# clock_mux.net
KiCad netlist of a schematic drawn in Altium Designer
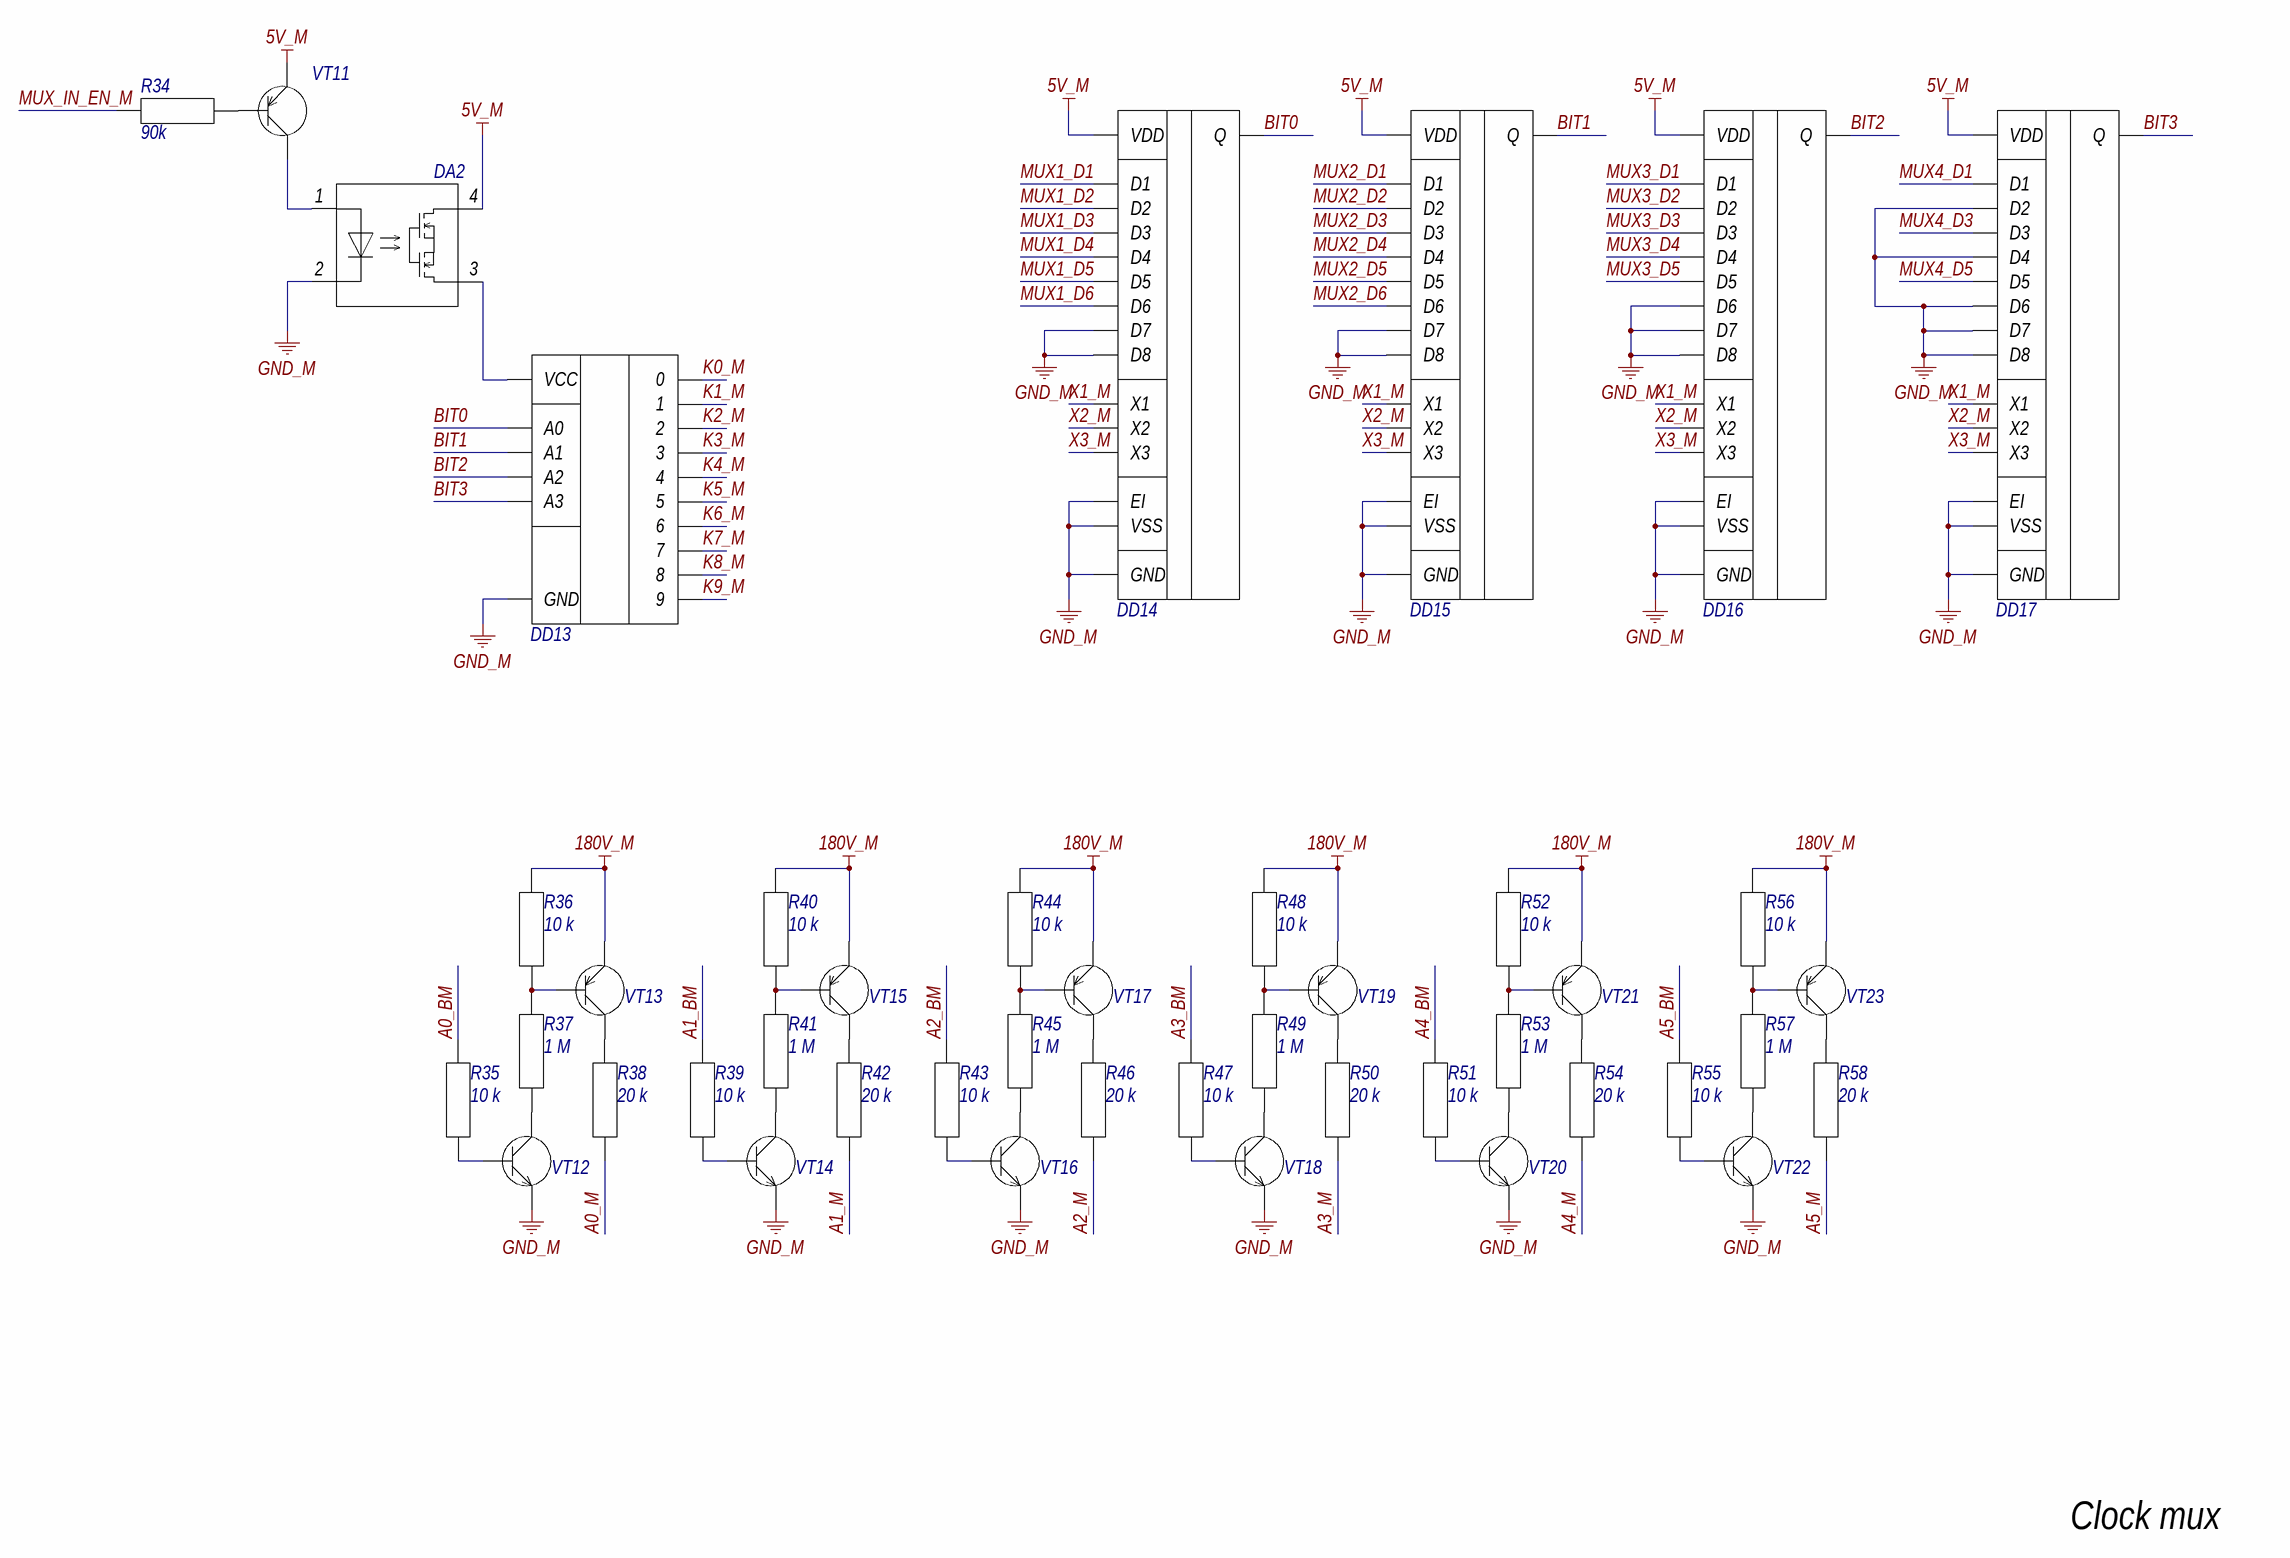
[diagram p0: clock_mux.SchDoc]

(export (version "E")
  (design (tool "Eeschema 10.0.6"))
  (components
    (comp (ref "DA2")
      (value "CPC1008NTR")
      (footprint "CPC1008NTR")
      (libsource (lib "Schlib1") (part "CPC1008NTR"))
    )
    (comp (ref "DD13") (value "К155ИД1") (footprint "DIP-16") (libsource (lib "Schlib1") (part "К155ИД1")))
    (comp (ref "DD14") (value "К561КП2") (footprint "DIP-16") (libsource (lib "Schlib1") (part "К561КП2")))
    (comp (ref "DD15") (value "К561КП2") (footprint "DIP-16") (libsource (lib "Schlib1") (part "К561КП2")))
    (comp (ref "DD16") (value "К561КП2") (footprint "DIP-16") (libsource (lib "Schlib1") (part "К561КП2")))
    (comp (ref "DD17") (value "К561КП2") (footprint "DIP-16") (libsource (lib "Schlib1") (part "К561КП2")))
    (comp (ref "R34")
      (value "90k")
      (footprint "RES-DIP")
      (fields (field (name "Comment") "R"))
      (libsource (lib "") (part "R_2"))
    )
    (comp (ref "R35")
      (value "10 k")
      (footprint "RES-DIP-V")
      (fields (field (name "Comment") "R"))
      (libsource (lib "") (part "R_1"))
    )
    (comp (ref "R36")
      (value "10 k")
      (footprint "RES-DIP-V")
      (fields (field (name "Comment") "R"))
      (libsource (lib "Schlib1") (part "R"))
    )
    (comp (ref "R37")
      (value "1 M")
      (footprint "RES-DIP-V")
      (fields (field (name "Comment") "R"))
      (libsource (lib "Schlib1") (part "R"))
    )
    (comp (ref "R38")
      (value "20 k")
      (footprint "RES-DIP-V")
      (fields (field (name "Comment") "R"))
      (libsource (lib "Schlib1") (part "R"))
    )
    (comp (ref "R39")
      (value "10 k")
      (footprint "RES-DIP-V")
      (fields (field (name "Comment") "R"))
      (libsource (lib "") (part "R_1"))
    )
    (comp (ref "R40")
      (value "10 k")
      (footprint "RES-DIP-V")
      (fields (field (name "Comment") "R"))
      (libsource (lib "Schlib1") (part "R"))
    )
    (comp (ref "R41")
      (value "1 M")
      (footprint "RES-DIP-V")
      (fields (field (name "Comment") "R"))
      (libsource (lib "Schlib1") (part "R"))
    )
    (comp (ref "R42")
      (value "20 k")
      (footprint "RES-DIP-V")
      (fields (field (name "Comment") "R"))
      (libsource (lib "Schlib1") (part "R"))
    )
    (comp (ref "R43")
      (value "10 k")
      (footprint "RES-DIP-V")
      (fields (field (name "Comment") "R"))
      (libsource (lib "") (part "R_1"))
    )
    (comp (ref "R44")
      (value "10 k")
      (footprint "RES-DIP-V")
      (fields (field (name "Comment") "R"))
      (libsource (lib "Schlib1") (part "R"))
    )
    (comp (ref "R45")
      (value "1 M")
      (footprint "RES-DIP-V")
      (fields (field (name "Comment") "R"))
      (libsource (lib "Schlib1") (part "R"))
    )
    (comp (ref "R46")
      (value "20 k")
      (footprint "RES-DIP-V")
      (fields (field (name "Comment") "R"))
      (libsource (lib "Schlib1") (part "R"))
    )
    (comp (ref "R47")
      (value "10 k")
      (footprint "RES-DIP-V")
      (fields (field (name "Comment") "R"))
      (libsource (lib "") (part "R_1"))
    )
    (comp (ref "R48")
      (value "10 k")
      (footprint "RES-DIP-V")
      (fields (field (name "Comment") "R"))
      (libsource (lib "Schlib1") (part "R"))
    )
    (comp (ref "R49")
      (value "1 M")
      (footprint "RES-DIP-V")
      (fields (field (name "Comment") "R"))
      (libsource (lib "Schlib1") (part "R"))
    )
    (comp (ref "R50")
      (value "20 k")
      (footprint "RES-DIP-V")
      (fields (field (name "Comment") "R"))
      (libsource (lib "Schlib1") (part "R"))
    )
    (comp (ref "R51")
      (value "10 k")
      (footprint "RES-DIP-V")
      (fields (field (name "Comment") "R"))
      (libsource (lib "") (part "R_1"))
    )
    (comp (ref "R52")
      (value "10 k")
      (footprint "RES-DIP-V")
      (fields (field (name "Comment") "R"))
      (libsource (lib "Schlib1") (part "R"))
    )
    (comp (ref "R53")
      (value "1 M")
      (footprint "RES-DIP-V")
      (fields (field (name "Comment") "R"))
      (libsource (lib "Schlib1") (part "R"))
    )
    (comp (ref "R54")
      (value "20 k")
      (footprint "RES-DIP-V")
      (fields (field (name "Comment") "R"))
      (libsource (lib "Schlib1") (part "R"))
    )
    (comp (ref "R55")
      (value "10 k")
      (footprint "RES-DIP-V")
      (fields (field (name "Comment") "R"))
      (libsource (lib "") (part "R_1"))
    )
    (comp (ref "R56")
      (value "10 k")
      (footprint "RES-DIP-V")
      (fields (field (name "Comment") "R"))
      (libsource (lib "Schlib1") (part "R"))
    )
    (comp (ref "R57")
      (value "1 M")
      (footprint "RES-DIP-V")
      (fields (field (name "Comment") "R"))
      (libsource (lib "Schlib1") (part "R"))
    )
    (comp (ref "R58")
      (value "20 k")
      (footprint "RES-DIP-V")
      (fields (field (name "Comment") "R"))
      (libsource (lib "Schlib1") (part "R"))
    )
    (comp (ref "VT11") (value "BC327") (footprint "BC327") (libsource (lib "Schlib1") (part "BC327")))
    (comp (ref "VT12") (value "2N5551") (footprint "2N5551") (libsource (lib "Schlib1") (part "2N5551")))
    (comp (ref "VT13") (value "2N5401") (footprint "2N5401") (libsource (lib "Schlib1") (part "2N5401")))
    (comp (ref "VT14") (value "2N5551") (footprint "2N5551") (libsource (lib "Schlib1") (part "2N5551")))
    (comp (ref "VT15") (value "2N5401") (footprint "2N5401") (libsource (lib "Schlib1") (part "2N5401")))
    (comp (ref "VT16") (value "2N5551") (footprint "2N5551") (libsource (lib "Schlib1") (part "2N5551")))
    (comp (ref "VT17") (value "2N5401") (footprint "2N5401") (libsource (lib "Schlib1") (part "2N5401")))
    (comp (ref "VT18") (value "2N5551") (footprint "2N5551") (libsource (lib "Schlib1") (part "2N5551")))
    (comp (ref "VT19") (value "2N5401") (footprint "2N5401") (libsource (lib "Schlib1") (part "2N5401")))
    (comp (ref "VT20") (value "2N5551") (footprint "2N5551") (libsource (lib "Schlib1") (part "2N5551")))
    (comp (ref "VT21") (value "2N5401") (footprint "2N5401") (libsource (lib "Schlib1") (part "2N5401")))
    (comp (ref "VT22") (value "2N5551") (footprint "2N5551") (libsource (lib "Schlib1") (part "2N5551")))
    (comp (ref "VT23") (value "2N5401") (footprint "2N5401") (libsource (lib "Schlib1") (part "2N5401")))
  )
  (nets
    (net (code "1") (name "/A0_BM") (class "Default")
      (node (ref "R35") (pin "1") (pinfunction "1_1") (pintype "passive"))
    )
    (net (code "2") (name "/A0_M") (class "Default")
      (node (ref "R38") (pin "1") (pinfunction "1_1") (pintype "passive"))
    )
    (net (code "3") (name "/A1_BM") (class "Default")
      (node (ref "R39") (pin "1") (pinfunction "1_1") (pintype "passive"))
    )
    (net (code "4") (name "/A1_M") (class "Default")
      (node (ref "R42") (pin "1") (pinfunction "1_1") (pintype "passive"))
    )
    (net (code "5") (name "/A2_BM") (class "Default")
      (node (ref "R43") (pin "1") (pinfunction "1_1") (pintype "passive"))
    )
    (net (code "6") (name "/A2_M") (class "Default")
      (node (ref "R46") (pin "1") (pinfunction "1_1") (pintype "passive"))
    )
    (net (code "7") (name "/A3_BM") (class "Default")
      (node (ref "R47") (pin "1") (pinfunction "1_1") (pintype "passive"))
    )
    (net (code "8") (name "/A3_M") (class "Default")
      (node (ref "R50") (pin "1") (pinfunction "1_1") (pintype "passive"))
    )
    (net (code "9") (name "/A4_BM") (class "Default")
      (node (ref "R51") (pin "1") (pinfunction "1_1") (pintype "passive"))
    )
    (net (code "10") (name "/A4_M") (class "Default")
      (node (ref "R54") (pin "1") (pinfunction "1_1") (pintype "passive"))
    )
    (net (code "11") (name "/A5_BM") (class "Default")
      (node (ref "R55") (pin "1") (pinfunction "1_1") (pintype "passive"))
    )
    (net (code "12") (name "/A5_M") (class "Default")
      (node (ref "R58") (pin "1") (pinfunction "1_1") (pintype "passive"))
    )
    (net (code "13") (name "/BIT0") (class "Default")
      (node (ref "DD13") (pin "3") (pinfunction "A0_3") (pintype "passive"))
      (node (ref "DD14") (pin "3") (pinfunction "Q_3") (pintype "passive"))
    )
    (net (code "14") (name "/BIT1") (class "Default")
      (node (ref "DD13") (pin "6") (pinfunction "A1_6") (pintype "passive"))
      (node (ref "DD15") (pin "3") (pinfunction "Q_3") (pintype "passive"))
    )
    (net (code "15") (name "/BIT2") (class "Default")
      (node (ref "DD13") (pin "7") (pinfunction "A2_7") (pintype "passive"))
      (node (ref "DD16") (pin "3") (pinfunction "Q_3") (pintype "passive"))
    )
    (net (code "16") (name "/BIT3") (class "Default")
      (node (ref "DD13") (pin "4") (pinfunction "A3_4") (pintype "passive"))
      (node (ref "DD17") (pin "3") (pinfunction "Q_3") (pintype "passive"))
    )
    (net (code "17") (name "/K0_M") (class "Default")
      (node (ref "DD13") (pin "16") (pinfunction "0_16") (pintype "passive"))
    )
    (net (code "18") (name "/K1_M") (class "Default")
      (node (ref "DD13") (pin "15") (pinfunction "1_15") (pintype "passive"))
    )
    (net (code "19") (name "/K2_M") (class "Default")
      (node (ref "DD13") (pin "8") (pinfunction "2_8") (pintype "passive"))
    )
    (net (code "20") (name "/K3_M") (class "Default")
      (node (ref "DD13") (pin "9") (pinfunction "3_9") (pintype "passive"))
    )
    (net (code "21") (name "/K4_M") (class "Default")
      (node (ref "DD13") (pin "13") (pinfunction "4_13") (pintype "passive"))
    )
    (net (code "22") (name "/K5_M") (class "Default")
      (node (ref "DD13") (pin "14") (pinfunction "5_14") (pintype "passive"))
    )
    (net (code "23") (name "/K6_M") (class "Default")
      (node (ref "DD13") (pin "11") (pinfunction "6_11") (pintype "passive"))
    )
    (net (code "24") (name "/K7_M") (class "Default")
      (node (ref "DD13") (pin "10") (pinfunction "7_10") (pintype "passive"))
    )
    (net (code "25") (name "/K8_M") (class "Default")
      (node (ref "DD13") (pin "1") (pinfunction "8_1") (pintype "passive"))
    )
    (net (code "26") (name "/K9_M") (class "Default")
      (node (ref "DD13") (pin "2") (pinfunction "9_2") (pintype "passive"))
    )
    (net (code "27") (name "/MUX1_D1") (class "Default")
      (node (ref "DD14") (pin "13") (pinfunction "D1_13") (pintype "passive"))
    )
    (net (code "28") (name "/MUX1_D2") (class "Default")
      (node (ref "DD14") (pin "14") (pinfunction "D2_14") (pintype "passive"))
    )
    (net (code "29") (name "/MUX1_D3") (class "Default")
      (node (ref "DD14") (pin "15") (pinfunction "D3_15") (pintype "passive"))
    )
    (net (code "30") (name "/MUX1_D4") (class "Default")
      (node (ref "DD14") (pin "12") (pinfunction "D4_12") (pintype "passive"))
    )
    (net (code "31") (name "/MUX1_D5") (class "Default")
      (node (ref "DD14") (pin "1") (pinfunction "D5_1") (pintype "passive"))
    )
    (net (code "32") (name "/MUX1_D6") (class "Default")
      (node (ref "DD14") (pin "5") (pinfunction "D6_5") (pintype "passive"))
    )
    (net (code "33") (name "/MUX2_D1") (class "Default")
      (node (ref "DD15") (pin "13") (pinfunction "D1_13") (pintype "passive"))
    )
    (net (code "34") (name "/MUX2_D2") (class "Default")
      (node (ref "DD15") (pin "14") (pinfunction "D2_14") (pintype "passive"))
    )
    (net (code "35") (name "/MUX2_D3") (class "Default")
      (node (ref "DD15") (pin "15") (pinfunction "D3_15") (pintype "passive"))
    )
    (net (code "36") (name "/MUX2_D4") (class "Default")
      (node (ref "DD15") (pin "12") (pinfunction "D4_12") (pintype "passive"))
    )
    (net (code "37") (name "/MUX2_D5") (class "Default")
      (node (ref "DD15") (pin "1") (pinfunction "D5_1") (pintype "passive"))
    )
    (net (code "38") (name "/MUX2_D6") (class "Default")
      (node (ref "DD15") (pin "5") (pinfunction "D6_5") (pintype "passive"))
    )
    (net (code "39") (name "/MUX3_D1") (class "Default")
      (node (ref "DD16") (pin "13") (pinfunction "D1_13") (pintype "passive"))
    )
    (net (code "40") (name "/MUX3_D2") (class "Default")
      (node (ref "DD16") (pin "14") (pinfunction "D2_14") (pintype "passive"))
    )
    (net (code "41") (name "/MUX3_D3") (class "Default")
      (node (ref "DD16") (pin "15") (pinfunction "D3_15") (pintype "passive"))
    )
    (net (code "42") (name "/MUX3_D4") (class "Default")
      (node (ref "DD16") (pin "12") (pinfunction "D4_12") (pintype "passive"))
    )
    (net (code "43") (name "/MUX3_D5") (class "Default")
      (node (ref "DD16") (pin "1") (pinfunction "D5_1") (pintype "passive"))
    )
    (net (code "44") (name "/MUX4_D1") (class "Default")
      (node (ref "DD17") (pin "13") (pinfunction "D1_13") (pintype "passive"))
    )
    (net (code "45") (name "/MUX4_D3") (class "Default")
      (node (ref "DD17") (pin "15") (pinfunction "D3_15") (pintype "passive"))
    )
    (net (code "46") (name "/MUX4_D5") (class "Default")
      (node (ref "DD17") (pin "1") (pinfunction "D5_1") (pintype "passive"))
    )
    (net (code "47") (name "/MUX_IN_EN_M") (class "Default")
      (node (ref "R34") (pin "1") (pinfunction "1_1") (pintype "passive"))
    )
    (net (code "48") (name "/X1_M") (class "Default")
      (node (ref "DD14") (pin "11") (pinfunction "X1_11") (pintype "passive"))
      (node (ref "DD15") (pin "11") (pinfunction "X1_11") (pintype "passive"))
      (node (ref "DD16") (pin "11") (pinfunction "X1_11") (pintype "passive"))
      (node (ref "DD17") (pin "11") (pinfunction "X1_11") (pintype "passive"))
    )
    (net (code "49") (name "/X2_M") (class "Default")
      (node (ref "DD14") (pin "10") (pinfunction "X2_10") (pintype "passive"))
      (node (ref "DD15") (pin "10") (pinfunction "X2_10") (pintype "passive"))
      (node (ref "DD16") (pin "10") (pinfunction "X2_10") (pintype "passive"))
      (node (ref "DD17") (pin "10") (pinfunction "X2_10") (pintype "passive"))
    )
    (net (code "50") (name "/X3_M") (class "Default")
      (node (ref "DD14") (pin "9") (pinfunction "X3_9") (pintype "passive"))
      (node (ref "DD15") (pin "9") (pinfunction "X3_9") (pintype "passive"))
      (node (ref "DD16") (pin "9") (pinfunction "X3_9") (pintype "passive"))
      (node (ref "DD17") (pin "9") (pinfunction "X3_9") (pintype "passive"))
    )
    (net (code "51") (name "5V_M") (class "Default")
      (node (ref "DA2") (pin "4") (pinfunction "4_4") (pintype "passive"))
      (node (ref "DD14") (pin "16") (pinfunction "VDD_16") (pintype "passive"))
      (node (ref "DD15") (pin "16") (pinfunction "VDD_16") (pintype "passive"))
      (node (ref "DD16") (pin "16") (pinfunction "VDD_16") (pintype "passive"))
      (node (ref "DD17") (pin "16") (pinfunction "VDD_16") (pintype "passive"))
      (node (ref "VT11") (pin "3") (pinfunction "E_3") (pintype "passive"))
    )
    (net (code "52") (name "180V_M") (class "Default")
      (node (ref "R36") (pin "2") (pinfunction "2_2") (pintype "passive"))
      (node (ref "R40") (pin "2") (pinfunction "2_2") (pintype "passive"))
      (node (ref "R44") (pin "2") (pinfunction "2_2") (pintype "passive"))
      (node (ref "R48") (pin "2") (pinfunction "2_2") (pintype "passive"))
      (node (ref "R52") (pin "2") (pinfunction "2_2") (pintype "passive"))
      (node (ref "R56") (pin "2") (pinfunction "2_2") (pintype "passive"))
      (node (ref "VT13") (pin "1") (pinfunction "E_1") (pintype "passive"))
      (node (ref "VT15") (pin "1") (pinfunction "E_1") (pintype "passive"))
      (node (ref "VT17") (pin "1") (pinfunction "E_1") (pintype "passive"))
      (node (ref "VT19") (pin "1") (pinfunction "E_1") (pintype "passive"))
      (node (ref "VT21") (pin "1") (pinfunction "E_1") (pintype "passive"))
      (node (ref "VT23") (pin "1") (pinfunction "E_1") (pintype "passive"))
    )
    (net (code "53") (name "GND_M") (class "Default")
      (node (ref "DA2") (pin "2") (pinfunction "2_2") (pintype "passive"))
      (node (ref "DD13") (pin "12") (pinfunction "GND_12") (pintype "passive"))
      (node (ref "DD14") (pin "2") (pinfunction "D7_2") (pintype "passive"))
      (node (ref "DD14") (pin "4") (pinfunction "D8_4") (pintype "passive"))
      (node (ref "DD14") (pin "6") (pinfunction "EI_6") (pintype "passive"))
      (node (ref "DD14") (pin "7") (pinfunction "VSS_7") (pintype "passive"))
      (node (ref "DD14") (pin "8") (pinfunction "GND_8") (pintype "passive"))
      (node (ref "DD15") (pin "2") (pinfunction "D7_2") (pintype "passive"))
      (node (ref "DD15") (pin "4") (pinfunction "D8_4") (pintype "passive"))
      (node (ref "DD15") (pin "6") (pinfunction "EI_6") (pintype "passive"))
      (node (ref "DD15") (pin "7") (pinfunction "VSS_7") (pintype "passive"))
      (node (ref "DD15") (pin "8") (pinfunction "GND_8") (pintype "passive"))
      (node (ref "DD16") (pin "2") (pinfunction "D7_2") (pintype "passive"))
      (node (ref "DD16") (pin "4") (pinfunction "D8_4") (pintype "passive"))
      (node (ref "DD16") (pin "5") (pinfunction "D6_5") (pintype "passive"))
      (node (ref "DD16") (pin "6") (pinfunction "EI_6") (pintype "passive"))
      (node (ref "DD16") (pin "7") (pinfunction "VSS_7") (pintype "passive"))
      (node (ref "DD16") (pin "8") (pinfunction "GND_8") (pintype "passive"))
      (node (ref "DD17") (pin "12") (pinfunction "D4_12") (pintype "passive"))
      (node (ref "DD17") (pin "14") (pinfunction "D2_14") (pintype "passive"))
      (node (ref "DD17") (pin "2") (pinfunction "D7_2") (pintype "passive"))
      (node (ref "DD17") (pin "4") (pinfunction "D8_4") (pintype "passive"))
      (node (ref "DD17") (pin "5") (pinfunction "D6_5") (pintype "passive"))
      (node (ref "DD17") (pin "6") (pinfunction "EI_6") (pintype "passive"))
      (node (ref "DD17") (pin "7") (pinfunction "VSS_7") (pintype "passive"))
      (node (ref "DD17") (pin "8") (pinfunction "GND_8") (pintype "passive"))
      (node (ref "VT12") (pin "1") (pinfunction "E_1") (pintype "passive"))
      (node (ref "VT14") (pin "1") (pinfunction "E_1") (pintype "passive"))
      (node (ref "VT16") (pin "1") (pinfunction "E_1") (pintype "passive"))
      (node (ref "VT18") (pin "1") (pinfunction "E_1") (pintype "passive"))
      (node (ref "VT20") (pin "1") (pinfunction "E_1") (pintype "passive"))
      (node (ref "VT22") (pin "1") (pinfunction "E_1") (pintype "passive"))
    )
    (net (code "54") (name "Net-(DD13-VCC)") (class "Default")
      (node (ref "DA2") (pin "3") (pinfunction "3_3") (pintype "passive"))
      (node (ref "DD13") (pin "5") (pinfunction "VCC_5") (pintype "passive"))
    )
    (net (code "55") (name "Net-(VT11-B)") (class "Default")
      (node (ref "R34") (pin "2") (pinfunction "2_2") (pintype "passive"))
      (node (ref "VT11") (pin "2") (pinfunction "B_2") (pintype "passive"))
    )
    (net (code "56") (name "Net-(VT11-C)") (class "Default")
      (node (ref "DA2") (pin "1") (pinfunction "1_1") (pintype "passive"))
      (node (ref "VT11") (pin "1") (pinfunction "C_1") (pintype "passive"))
    )
    (net (code "57") (name "Net-(VT12-B)") (class "Default")
      (node (ref "R35") (pin "2") (pinfunction "2_2") (pintype "passive"))
      (node (ref "VT12") (pin "2") (pinfunction "B_2") (pintype "passive"))
    )
    (net (code "58") (name "Net-(VT12-C)") (class "Default")
      (node (ref "R37") (pin "1") (pinfunction "1_1") (pintype "passive"))
      (node (ref "VT12") (pin "3") (pinfunction "C_3") (pintype "passive"))
    )
    (net (code "59") (name "Net-(VT13-B)") (class "Default")
      (node (ref "R36") (pin "1") (pinfunction "1_1") (pintype "passive"))
      (node (ref "R37") (pin "2") (pinfunction "2_2") (pintype "passive"))
      (node (ref "VT13") (pin "2") (pinfunction "B_2") (pintype "passive"))
    )
    (net (code "60") (name "Net-(VT13-C)") (class "Default")
      (node (ref "R38") (pin "2") (pinfunction "2_2") (pintype "passive"))
      (node (ref "VT13") (pin "3") (pinfunction "C_3") (pintype "passive"))
    )
    (net (code "61") (name "Net-(VT14-B)") (class "Default")
      (node (ref "R39") (pin "2") (pinfunction "2_2") (pintype "passive"))
      (node (ref "VT14") (pin "2") (pinfunction "B_2") (pintype "passive"))
    )
    (net (code "62") (name "Net-(VT14-C)") (class "Default")
      (node (ref "R41") (pin "1") (pinfunction "1_1") (pintype "passive"))
      (node (ref "VT14") (pin "3") (pinfunction "C_3") (pintype "passive"))
    )
    (net (code "63") (name "Net-(VT15-B)") (class "Default")
      (node (ref "R40") (pin "1") (pinfunction "1_1") (pintype "passive"))
      (node (ref "R41") (pin "2") (pinfunction "2_2") (pintype "passive"))
      (node (ref "VT15") (pin "2") (pinfunction "B_2") (pintype "passive"))
    )
    (net (code "64") (name "Net-(VT15-C)") (class "Default")
      (node (ref "R42") (pin "2") (pinfunction "2_2") (pintype "passive"))
      (node (ref "VT15") (pin "3") (pinfunction "C_3") (pintype "passive"))
    )
    (net (code "65") (name "Net-(VT16-B)") (class "Default")
      (node (ref "R43") (pin "2") (pinfunction "2_2") (pintype "passive"))
      (node (ref "VT16") (pin "2") (pinfunction "B_2") (pintype "passive"))
    )
    (net (code "66") (name "Net-(VT16-C)") (class "Default")
      (node (ref "R45") (pin "1") (pinfunction "1_1") (pintype "passive"))
      (node (ref "VT16") (pin "3") (pinfunction "C_3") (pintype "passive"))
    )
    (net (code "67") (name "Net-(VT17-B)") (class "Default")
      (node (ref "R44") (pin "1") (pinfunction "1_1") (pintype "passive"))
      (node (ref "R45") (pin "2") (pinfunction "2_2") (pintype "passive"))
      (node (ref "VT17") (pin "2") (pinfunction "B_2") (pintype "passive"))
    )
    (net (code "68") (name "Net-(VT17-C)") (class "Default")
      (node (ref "R46") (pin "2") (pinfunction "2_2") (pintype "passive"))
      (node (ref "VT17") (pin "3") (pinfunction "C_3") (pintype "passive"))
    )
    (net (code "69") (name "Net-(VT18-B)") (class "Default")
      (node (ref "R47") (pin "2") (pinfunction "2_2") (pintype "passive"))
      (node (ref "VT18") (pin "2") (pinfunction "B_2") (pintype "passive"))
    )
    (net (code "70") (name "Net-(VT18-C)") (class "Default")
      (node (ref "R49") (pin "1") (pinfunction "1_1") (pintype "passive"))
      (node (ref "VT18") (pin "3") (pinfunction "C_3") (pintype "passive"))
    )
    (net (code "71") (name "Net-(VT19-B)") (class "Default")
      (node (ref "R48") (pin "1") (pinfunction "1_1") (pintype "passive"))
      (node (ref "R49") (pin "2") (pinfunction "2_2") (pintype "passive"))
      (node (ref "VT19") (pin "2") (pinfunction "B_2") (pintype "passive"))
    )
    (net (code "72") (name "Net-(VT19-C)") (class "Default")
      (node (ref "R50") (pin "2") (pinfunction "2_2") (pintype "passive"))
      (node (ref "VT19") (pin "3") (pinfunction "C_3") (pintype "passive"))
    )
    (net (code "73") (name "Net-(VT20-B)") (class "Default")
      (node (ref "R51") (pin "2") (pinfunction "2_2") (pintype "passive"))
      (node (ref "VT20") (pin "2") (pinfunction "B_2") (pintype "passive"))
    )
    (net (code "74") (name "Net-(VT20-C)") (class "Default")
      (node (ref "R53") (pin "1") (pinfunction "1_1") (pintype "passive"))
      (node (ref "VT20") (pin "3") (pinfunction "C_3") (pintype "passive"))
    )
    (net (code "75") (name "Net-(VT21-B)") (class "Default")
      (node (ref "R52") (pin "1") (pinfunction "1_1") (pintype "passive"))
      (node (ref "R53") (pin "2") (pinfunction "2_2") (pintype "passive"))
      (node (ref "VT21") (pin "2") (pinfunction "B_2") (pintype "passive"))
    )
    (net (code "76") (name "Net-(VT21-C)") (class "Default")
      (node (ref "R54") (pin "2") (pinfunction "2_2") (pintype "passive"))
      (node (ref "VT21") (pin "3") (pinfunction "C_3") (pintype "passive"))
    )
    (net (code "77") (name "Net-(VT22-B)") (class "Default")
      (node (ref "R55") (pin "2") (pinfunction "2_2") (pintype "passive"))
      (node (ref "VT22") (pin "2") (pinfunction "B_2") (pintype "passive"))
    )
    (net (code "78") (name "Net-(VT22-C)") (class "Default")
      (node (ref "R57") (pin "1") (pinfunction "1_1") (pintype "passive"))
      (node (ref "VT22") (pin "3") (pinfunction "C_3") (pintype "passive"))
    )
    (net (code "79") (name "Net-(VT23-B)") (class "Default")
      (node (ref "R56") (pin "1") (pinfunction "1_1") (pintype "passive"))
      (node (ref "R57") (pin "2") (pinfunction "2_2") (pintype "passive"))
      (node (ref "VT23") (pin "2") (pinfunction "B_2") (pintype "passive"))
    )
    (net (code "80") (name "Net-(VT23-C)") (class "Default")
      (node (ref "R58") (pin "2") (pinfunction "2_2") (pintype "passive"))
      (node (ref "VT23") (pin "3") (pinfunction "C_3") (pintype "passive"))
    )
  )
)
